# Sheet1.net
KiCad netlist of a schematic drawn in Altium Designer
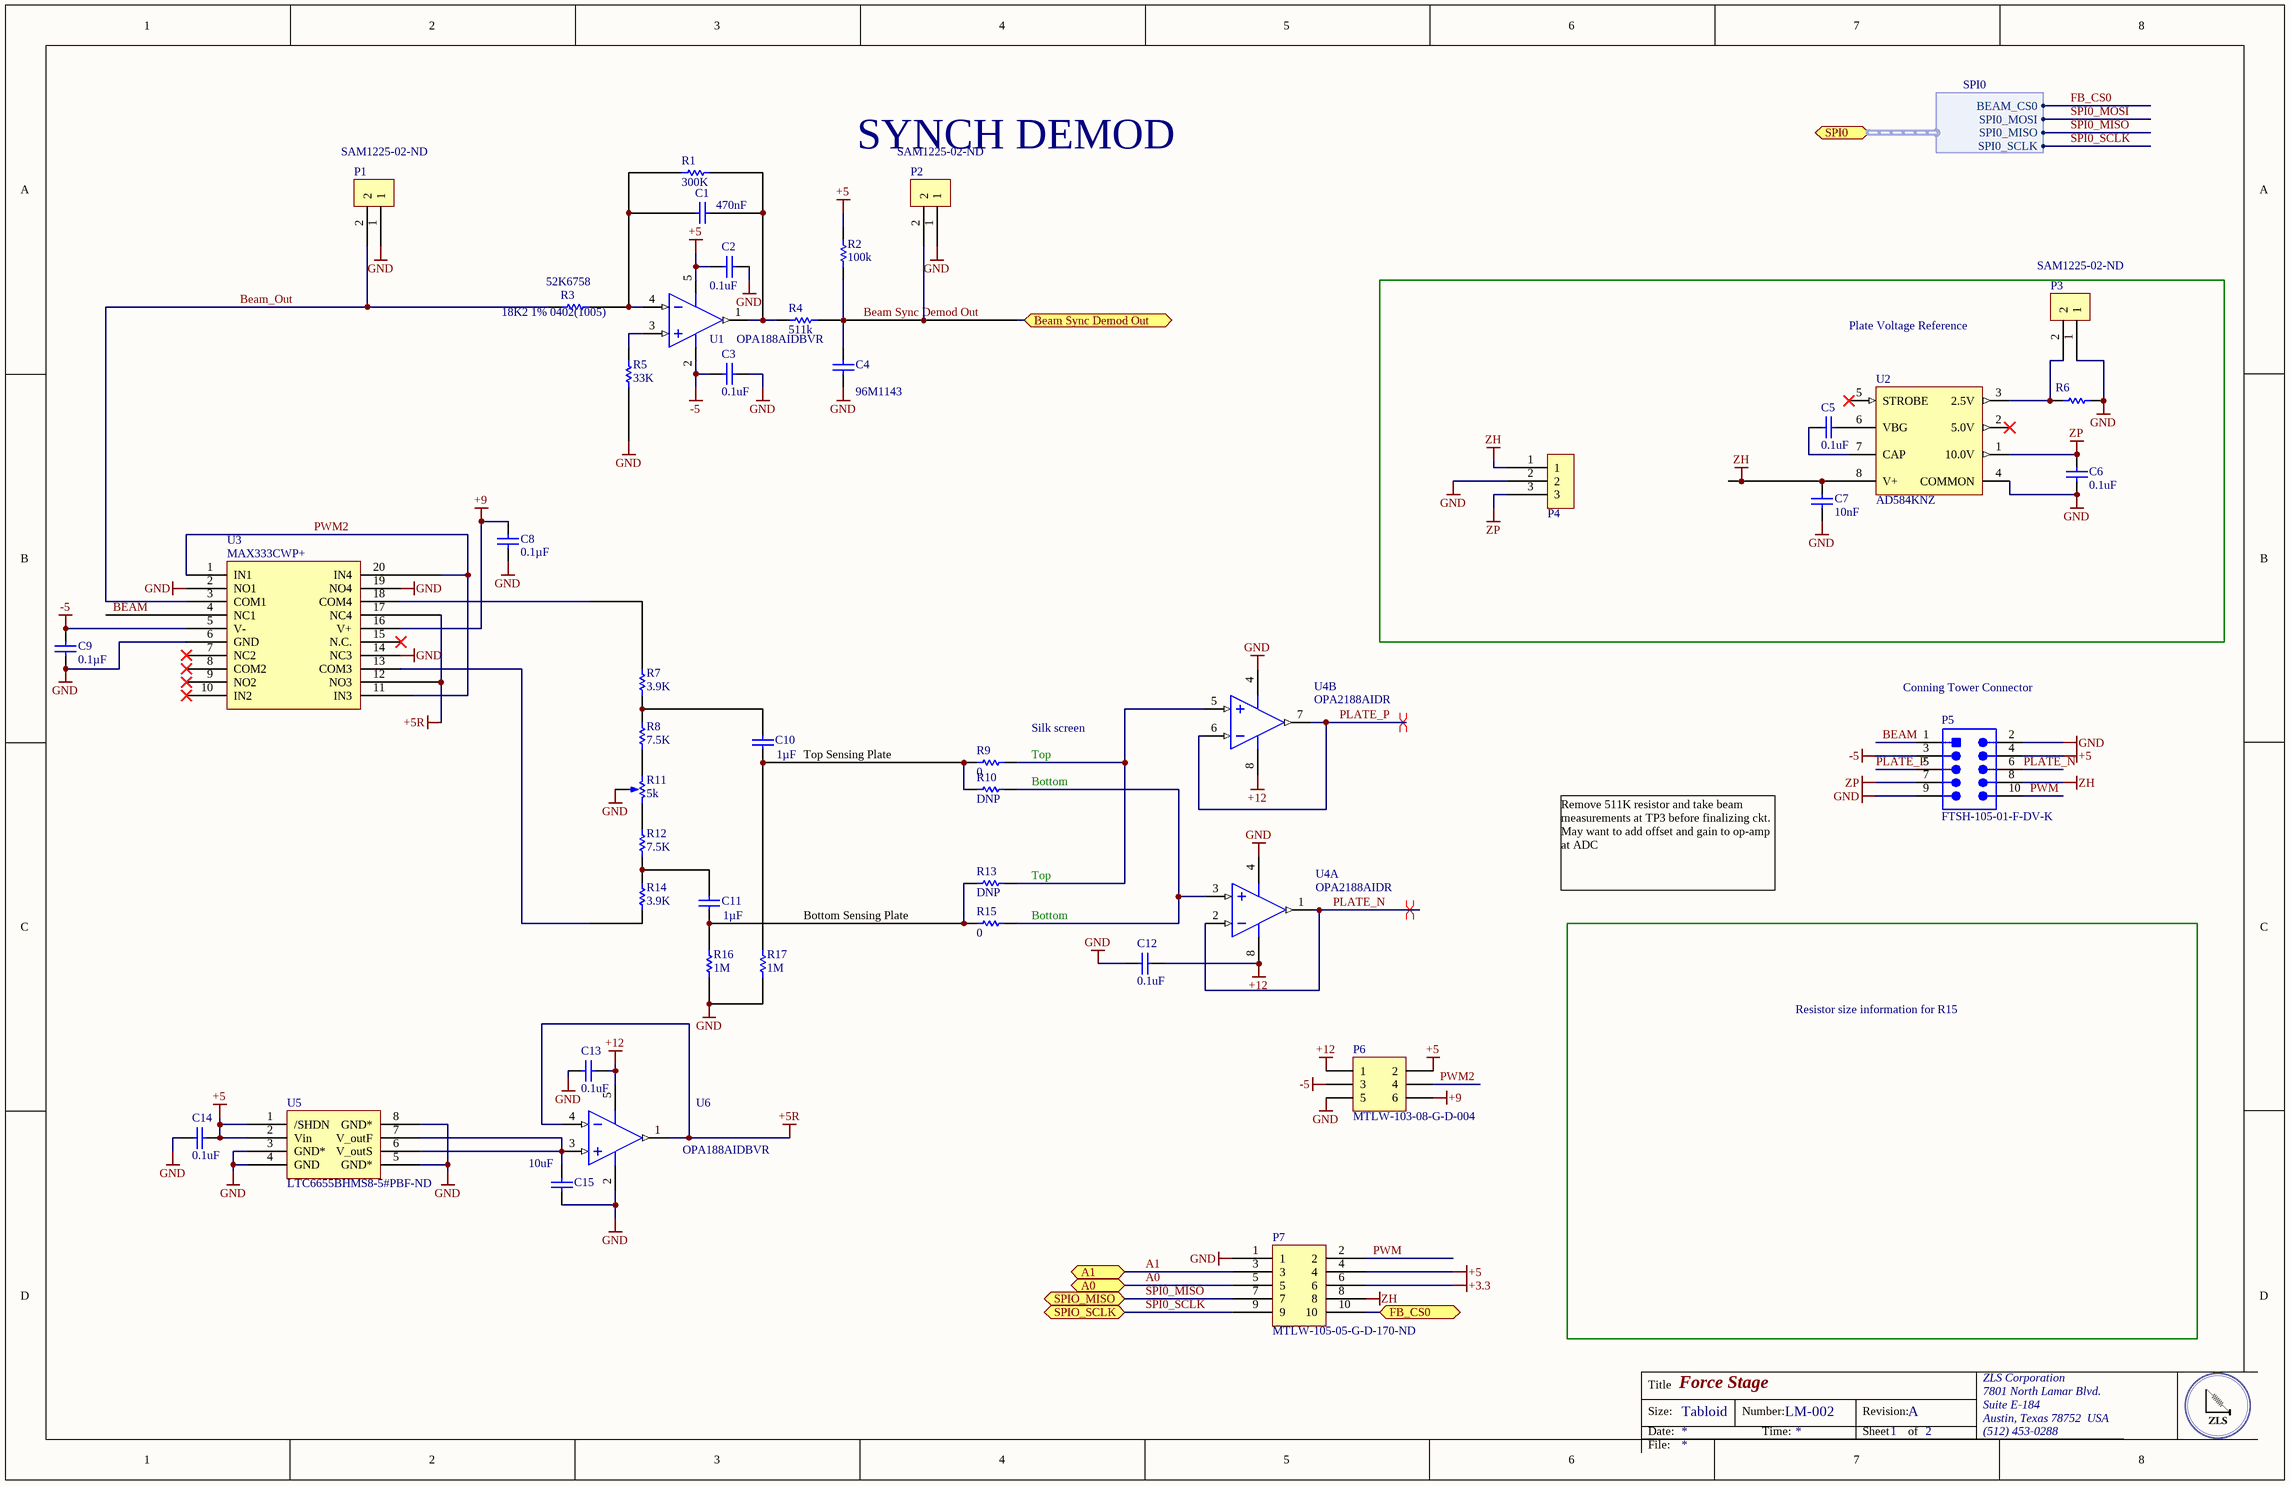
[diagram p0: Sheet1.SchDoc]

(export (version "E")
  (design (tool "Eeschema 10.0.6"))
  (components
    (comp (ref "C1")
      (value "~")
      (footprint "CAPC0402(1005)60_L")
      (fields
        (field (name "MANUFACTURER") "TDK")
        (field (name "MANUFACTURER PART NUMBER") "C1005X5R1E474M050BB")
        (field (name "TOLERANCE") "20%")
        (field (name "CAPACITANCE") "470nF")
      )
      (libsource (lib "Altium Content Vault") (part "CMP-1034-01343-1"))
    )
    (comp (ref "C2")
      (value "0.1uF")
      (footprint "CAPC0402(1005)60_L")
      (description "CAP CER 0.1UF 10V X7R 0402")
      (fields
        (field (name "MANUFACTURER") "Murata Electronics North America")
        (field (name "MANUFACTURER PART NUMBER") "GRM155R71A104KA01D")
      )
      (libsource (lib "Altium Content Vault") (part "CMP-1034-00252-1"))
    )
    (comp (ref "C3")
      (value "0.1uF")
      (footprint "CAPC0402(1005)60_L")
      (description "CAP CER 0.1UF 10V X7R 0402")
      (fields
        (field (name "MANUFACTURER") "Murata Electronics North America")
        (field (name "MANUFACTURER PART NUMBER") "GRM155R71A104KA01D")
      )
      (libsource (lib "Altium Content Vault") (part "CMP-1034-00252-1"))
    )
    (comp (ref "C4")
      (value "~")
      (footprint "CAPC0402(1005)60_L")
      (fields
        (field (name "SUPPLIER PART NUMBER 1") "96M1143")
        (field (name "MANUFACTURER") "AVX")
        (field (name "MANUFACTURER PART NUMBER") "04025A220JAT2A")
      )
      (libsource (lib "Altium Content Vault") (part "CMP-1034-01343-1"))
    )
    (comp (ref "C5")
      (value "0.1uF")
      (footprint "CAPC0402(1005)60_L")
      (description "CAP CER 0.1UF 10V X7R 0402")
      (fields
        (field (name "MANUFACTURER") "Murata Electronics North America")
        (field (name "MANUFACTURER PART NUMBER") "GRM155R71A104KA01D")
      )
      (libsource (lib "Altium Content Vault") (part "CMP-1034-00252-1"))
    )
    (comp (ref "C6")
      (value "0.1uF")
      (footprint "CAPC0402(1005)60_L")
      (description "CAP CER 0.1UF 10V X7R 0402")
      (fields
        (field (name "MANUFACTURER") "Murata Electronics North America")
        (field (name "MANUFACTURER PART NUMBER") "GRM155R71A104KA01D")
      )
      (libsource (lib "Altium Content Vault") (part "CMP-1034-00252-1"))
    )
    (comp (ref "C7")
      (value "Multilayer Ceramic Capacitors MLCC - SMD/SMT 0.01uF 50volts 10% X7R")
      (footprint "CAPC0805(2012)145_N")
      (fields
        (field (name "MANUFACTURER") "Kemet")
        (field (name "MANUFACTURER PART NUMBER") "C0805C103K5RACAUTO")
        (field (name "CAPACITANCE") "10nF")
        (field (name "TOLERANCE") "10%")
      )
      (libsource (lib "Altium Content Vault") (part "CMP-1036-04795-1"))
    )
    (comp (ref "C8")
      (value "CAP CER 0.1UF 25V X7R 0805")
      (footprint "CAPC0805(2012)145_N")
      (fields
        (field (name "MANUFACTURER") "Murata Electronics North America")
        (field (name "MANUFACTURER PART NUMBER") "GRM21BR71E104KA01L")
        (field (name "CAPACITANCE") "0.1µF")
        (field (name "TOLERANCE") "±10%")
      )
      (libsource (lib "Altium Content Vault") (part "CMP-1036-04795-1"))
    )
    (comp (ref "C9")
      (value "CAP CER 0.1UF 25V X7R 0805")
      (footprint "CAPC0805(2012)145_N")
      (fields
        (field (name "MANUFACTURER") "Murata Electronics North America")
        (field (name "MANUFACTURER PART NUMBER") "GRM21BR71E104KA01L")
        (field (name "CAPACITANCE") "0.1µF")
        (field (name "TOLERANCE") "±10%")
      )
      (libsource (lib "Altium Content Vault") (part "CMP-1036-04795-1"))
    )
    (comp (ref "C10")
      (value "CAP CER 1UF 25V X7R 0805")
      (footprint "CAPC0805(2012)155_L")
      (fields
        (field (name "MANUFACTURER") "Murata Electronics North America")
        (field (name "MANUFACTURER PART NUMBER") "GRM21BR71E105KA99L")
        (field (name "CAPACITANCE") "1µF")
        (field (name "TOLERANCE") "±10%")
      )
      (libsource (lib "Altium Content Vault") (part "CMP-1036-04882-1"))
    )
    (comp (ref "C11")
      (value "CAP CER 1UF 25V X7R 0805")
      (footprint "CAPC0805(2012)155_L")
      (fields
        (field (name "MANUFACTURER") "Murata Electronics North America")
        (field (name "MANUFACTURER PART NUMBER") "GRM21BR71E105KA99L")
        (field (name "CAPACITANCE") "1µF")
        (field (name "TOLERANCE") "±10%")
      )
      (libsource (lib "Altium Content Vault") (part "CMP-1036-04882-1"))
    )
    (comp (ref "C12")
      (value "0.1uF")
      (footprint "CAPC0402(1005)60_L")
      (description "CAP CER 0.1UF 10V X7R 0402")
      (fields
        (field (name "MANUFACTURER") "Murata Electronics North America")
        (field (name "MANUFACTURER PART NUMBER") "GRM155R71A104KA01D")
      )
      (libsource (lib "Altium Content Vault") (part "CMP-1034-00252-1"))
    )
    (comp (ref "C13")
      (value "0.1uF")
      (footprint "CAPC0402(1005)60_L")
      (description "CAP CER 0.1UF 10V X7R 0402")
      (fields
        (field (name "MANUFACTURER") "Murata Electronics North America")
        (field (name "MANUFACTURER PART NUMBER") "GRM155R71A104KA01D")
      )
      (libsource (lib "Altium Content Vault") (part "CMP-1034-00252-1"))
    )
    (comp (ref "C14")
      (value "0.1uF")
      (footprint "CAPC0402(1005)60_L")
      (description "CAP CER 0.1UF 10V X7R 0402")
      (fields
        (field (name "MANUFACTURER") "Murata Electronics North America")
        (field (name "MANUFACTURER PART NUMBER") "GRM155R71A104KA01D")
      )
      (libsource (lib "Altium Content Vault") (part "CMP-1034-00252-1"))
    )
    (comp (ref "C15")
      (value "10uF")
      (footprint "CAPC1812(4532)250_N")
      (description "CAP FILM 10UF 20% 16VDC 1812")
      (fields (field (name "TOLERANCE") "Â±10%") (field (name "MANUFACTURER") "Rubycon"))
      (libsource (lib "Altium Content Vault") (part "CMP-1040-01653-1"))
    )
    (comp (ref "P1")
      (value "SSW-102-02-G-S-RA")
      (footprint "SSW-102-02-G-S-RA")
      (fields (field (name "SUPPLIER PART NUMBER 1") "SAM1225-02-ND"))
      (libsource (lib "ZLS_Schematic_lib") (part "SSW-102-02-G-S-RA"))
    )
    (comp (ref "P2")
      (value "SSW-102-02-G-S-RA")
      (footprint "SSW-102-02-G-S-RA")
      (fields (field (name "SUPPLIER PART NUMBER 1") "SAM1225-02-ND"))
      (libsource (lib "ZLS_Schematic_lib") (part "SSW-102-02-G-S-RA"))
    )
    (comp (ref "P3")
      (value "SSW-102-02-G-S-RA")
      (footprint "SSW-102-02-G-S-RA")
      (fields (field (name "SUPPLIER PART NUMBER 1") "SAM1225-02-ND"))
      (libsource (lib "ZLS_Schematic_lib") (part "SSW-102-02-G-S-RA"))
    )
    (comp (ref "P4")
      (value "SSW-103-02-G-S-RA")
      (footprint "SSW-103-02-G-S-RA")
      (libsource (lib "ZLS_Schematic_lib") (part "SSW-103-02-G-S-RA"))
    )
    (comp (ref "P5")
      (value "FTSH-105-01-F-DV-K")
      (footprint "SMTC-FTSH-105-01-L-DV-K_V")
      (description "Male Header, Pitch 1.27 mm, 2 x 5 Position, Height 6.12 mm, RoHS, Tube")
      (fields (field (name "MANUFACTURER") "Samtec"))
      (libsource (lib "Altium Content Vault") (part "CN-2P-M-R10"))
    )
    (comp (ref "P6")
      (value "MTLW-103-08-G-D-004")
      (footprint "MTLW-103-08-G-D-004")
      (description "Header, 3-Pin, Dual row")
      (libsource (lib "Miscellaneous Connectors") (part "Header 3X2"))
    )
    (comp (ref "P7")
      (value "TLW-105-05-G-D")
      (footprint "TLW-105-05-G-D")
      (fields
        (field (name "SUPPLIER PART NUMBER 1") "MTLW-105-05-G-D-170-ND")
        (field (name "MANUFACTURER") "Samtec Inc.")
        (field (name "MANUFACTURER PART NUMBER") "MTLW-105-05-G-D-170")
      )
      (libsource (lib "ZLS_Schematic_lib") (part "TLW-105-05-G-D"))
    )
    (comp (ref "R1")
      (value "300K")
      (footprint "RESC0402(1005)_M")
      (libsource (lib "Altium Content Vault") (part "CMP-1011-00651-1"))
    )
    (comp (ref "R2")
      (value "100k")
      (footprint "RESC0402(1005)_M")
      (description "RES SMD 100K OHM 1% 1/8W 0402")
      (fields
        (field (name "MANUFACTURER") "Vishay Dale")
        (field (name "MANUFACTURER PART NUMBER") "CRCW0402100KFKEDHP")
      )
      (libsource (lib "Altium Content Vault") (part "CMP-1011-00651-1"))
    )
    (comp (ref "R3")
      (value "18K2 1% 0402(1005)")
      (footprint "RESC0402(1005)_M")
      (description "18K2 0.063W 1% 0402 (1005 Metric)  SMD")
      (fields
        (field (name "SUPPLIER PART NUMBER 1") "52K6758")
        (field (name "MANUFACTURER") "VISHAY")
        (field (name "MANUFACTURER PART NUMBER") "CRCW040218K2FKED")
      )
      (libsource (lib "Altium Content Vault") (part "CMP-1011-00651-1"))
    )
    (comp (ref "R4")
      (value "511k")
      (footprint "RESC0402(1005)_M")
      (libsource (lib "Altium Content Vault") (part "CMP-1011-00651-1"))
    )
    (comp (ref "R5")
      (value "33K")
      (footprint "RESC0402(1005)_M")
      (libsource (lib "Altium Content Vault") (part "CMP-1011-00651-1"))
    )
    (comp (ref "R6")
      (value "TBD")
      (footprint "VH102K")
      (libsource (lib "altium-import") (part "root_0_CMP-1013-00393-1_"))
    )
    (comp (ref "R7")
      (value "3.9K")
      (footprint "RESC0402(1005)_M")
      (libsource (lib "Altium Content Vault") (part "CMP-1011-00463-1"))
    )
    (comp (ref "R8")
      (value "7.5K")
      (footprint "RESC0402(1005)_M")
      (libsource (lib "Altium Content Vault") (part "CMP-1011-00463-1"))
    )
    (comp (ref "R9")
      (value "0")
      (footprint "RESC0402(1005)_M")
      (libsource (lib "Altium Content Vault") (part "CMP-1011-00651-1"))
    )
    (comp (ref "R10")
      (value "DNP")
      (footprint "RESC0402(1005)_M")
      (libsource (lib "Altium Content Vault") (part "CMP-1011-00651-1"))
    )
    (comp (ref "R11")
      (value "TRIMMER 5K OHM 0.25W PC PIN")
      (footprint "Trimmer 2.54")
      (fields
        (field (name "MANUFACTURER") "Vishay Foil Resistors (Division of Vishay Precision Group)")
        (field (name "MANUFACTURER PART NUMBER") "Y00535K00000J0L")
        (field (name "RESISTANCE (OHMS)") "5k")
        (field (name "TOLERANCE") "±5%")
      )
      (libsource (lib "ZLS_Schematic_lib") (part "Trimmer"))
    )
    (comp (ref "R12")
      (value "7.5K")
      (footprint "RESC0402(1005)_M")
      (libsource (lib "Altium Content Vault") (part "CMP-1011-00463-1"))
    )
    (comp (ref "R13")
      (value "DNP")
      (footprint "RESC0402(1005)_M")
      (libsource (lib "Altium Content Vault") (part "CMP-1011-00651-1"))
    )
    (comp (ref "R14")
      (value "3.9K")
      (footprint "RESC0402(1005)_M")
      (libsource (lib "Altium Content Vault") (part "CMP-1011-00463-1"))
    )
    (comp (ref "R15")
      (value "0")
      (footprint "RESC0402(1005)_M")
      (libsource (lib "Altium Content Vault") (part "CMP-1011-00651-1"))
    )
    (comp (ref "R16")
      (value "1M")
      (footprint "RESC0402(1005)_M")
      (libsource (lib "Altium Content Vault") (part "CMP-1011-00463-1"))
    )
    (comp (ref "R17")
      (value "1M")
      (footprint "RESC0402(1005)_M")
      (libsource (lib "Altium Content Vault") (part "CMP-1011-00463-1"))
    )
    (comp (ref "U1")
      (value "OPA188AIDBVR")
      (footprint "DBV0005A_M")
      (fields (field (name "MANUFACTURER") "Texas Instruments"))
      (libsource (lib "Altium Content Vault") (part "CMP-0809-00005-2"))
    )
    (comp (ref "U2")
      (value "AD584KNZ")
      (footprint "ADI-N-8")
      (fields (field (name "MANUFACTURER") "Analog Devices"))
      (libsource (lib "Altium Content Vault") (part "ADI-AD584-N-8"))
    )
    (comp (ref "U3")
      (value "MAX333CWP+")
      (footprint "TSOP65P640X90-20N")
      (description "IC SWITCH QUAD SPDT 20TSSOP")
      (fields (field (name "MANUFACTURER") "Maxim") (field (name "MANUFACTURER PART NUMBER") "MAX333AEUP+"))
      (libsource (lib "ZLS_Schematic_lib") (part "MAX333CWP+"))
    )
    (comp (ref "U4")
      (value "OPA2188AIDR")
      (footprint "D0008A_L")
      (fields (field (name "MANUFACTURER") "Texas Instruments"))
      (libsource (lib "Altium Content Vault") (part "CMP-0272-00241-3"))
    )
    (comp (ref "U5")
      (value "LTC6655BHMS8-5#PBF")
      (footprint "TSOP65P490X110-8N")
      (fields
        (field (name "SUPPLIER PART NUMBER 1") "LTC6655BHMS8-5#PBF-ND")
        (field (name "MANUFACTURER") "Linear Technology")
        (field (name "TOLERANCE") "±0.025%")
      )
      (libsource (lib "ZLS_Schematic_lib") (part "LTC6655BHMS8-5#PBF"))
    )
    (comp (ref "U6")
      (value "OPA188AIDBVR")
      (footprint "DBV0005A_M")
      (fields (field (name "MANUFACTURER") "Texas Instruments"))
      (libsource (lib "Altium Content Vault") (part "CMP-0809-00005-2"))
    )
  )
  (nets
    (net (code "2") (name "+3.3") (class "Default")
      (node (ref "P7") (pin "6") (pinfunction "6_6") (pintype "passive"))
    )
    (net (code "3") (name "+5") (class "Default")
      (node (ref "C14") (pin "2") (pinfunction "2_2") (pintype "passive"))
      (node (ref "C2") (pin "1") (pinfunction "1_1") (pintype "passive"))
      (node (ref "P5") (pin "4") (pinfunction "4_4") (pintype "passive"))
      (node (ref "P6") (pin "2") (pinfunction "2_2") (pintype "passive"))
      (node (ref "P7") (pin "4") (pinfunction "4_4") (pintype "passive"))
      (node (ref "R2") (pin "2") (pinfunction "2_2") (pintype "passive"))
      (node (ref "U1") (pin "5") (pinfunction "V+_5") (pintype "power_in"))
      (node (ref "U5") (pin "1") (pinfunction "/SHDN_1") (pintype "passive"))
      (node (ref "U5") (pin "2") (pinfunction "Vin_2") (pintype "passive"))
    )
    (net (code "4") (name "+5R") (class "Default")
      (node (ref "U3") (pin "12") (pinfunction "NO3_12") (pintype "passive"))
      (node (ref "U3") (pin "17") (pinfunction "NC4_17") (pintype "passive"))
      (node (ref "U6") (pin "1") (pinfunction "OUT_1") (pintype "output"))
      (node (ref "U6") (pin "4") (pinfunction "IN-_4") (pintype "input"))
    )
    (net (code "5") (name "+9") (class "Default")
      (node (ref "C8") (pin "2") (pinfunction "2_2") (pintype "passive"))
      (node (ref "P6") (pin "6") (pinfunction "6_6") (pintype "passive"))
      (node (ref "U3") (pin "16") (pinfunction "V+_16") (pintype "power_in"))
    )
    (net (code "6") (name "+12") (class "Default")
      (node (ref "C12") (pin "2") (pinfunction "2_2") (pintype "passive"))
      (node (ref "C13") (pin "2") (pinfunction "2_2") (pintype "passive"))
      (node (ref "P6") (pin "1") (pinfunction "1_1") (pintype "passive"))
      (node (ref "U4") (pin "8") (pinfunction "V+_8") (pintype "power_in"))
      (node (ref "U6") (pin "5") (pinfunction "V+_5") (pintype "power_in"))
    )
    (net (code "7") (name "-5") (class "Default")
      (node (ref "C3") (pin "1") (pinfunction "1_1") (pintype "passive"))
      (node (ref "C9") (pin "1") (pinfunction "1_1") (pintype "passive"))
      (node (ref "P5") (pin "3") (pinfunction "3_3") (pintype "passive"))
      (node (ref "P6") (pin "3") (pinfunction "3_3") (pintype "passive"))
      (node (ref "U1") (pin "2") (pinfunction "V-_2") (pintype "power_in"))
      (node (ref "U3") (pin "5") (pinfunction "V-_5") (pintype "power_in"))
    )
    (net (code "8") (name "/A0") (class "Default")
      (node (ref "P7") (pin "5") (pinfunction "5_5") (pintype "passive"))
    )
    (net (code "9") (name "/A1") (class "Default")
      (node (ref "P7") (pin "3") (pinfunction "3_3") (pintype "passive"))
    )
    (net (code "10") (name "/BEAM") (class "Default")
      (node (ref "P5") (pin "1") (pinfunction "1_1") (pintype "passive"))
      (node (ref "U3") (pin "4") (pinfunction "NC1_4") (pintype "passive"))
    )
    (net (code "11") (name "/Beam Sync Demod Out") (class "Default")
      (node (ref "C4") (pin "2") (pinfunction "2_2") (pintype "passive"))
      (node (ref "P2") (pin "2") (pinfunction "2_2") (pintype "passive"))
      (node (ref "R2") (pin "1") (pinfunction "1_1") (pintype "passive"))
      (node (ref "R4") (pin "2") (pinfunction "2_2") (pintype "passive"))
    )
    (net (code "12") (name "/Beam_Out") (class "Default")
      (node (ref "P1") (pin "2") (pinfunction "2_2") (pintype "passive"))
      (node (ref "R3") (pin "1") (pinfunction "1_1") (pintype "passive"))
      (node (ref "U3") (pin "3") (pinfunction "COM1_3") (pintype "passive"))
    )
    (net (code "13") (name "/FB_CS0") (class "Default")
      (node (ref "P7") (pin "10") (pinfunction "10_10") (pintype "passive"))
    )
    (net (code "14") (name "/PLATE_N") (class "Default")
      (node (ref "P5") (pin "6") (pinfunction "6_6") (pintype "passive"))
      (node (ref "U4") (pin "1") (pinfunction "OUT_A_1") (pintype "output"))
      (node (ref "U4") (pin "2") (pinfunction "IN_A-_2") (pintype "input"))
    )
    (net (code "15") (name "/PLATE_P") (class "Default")
      (node (ref "P5") (pin "5") (pinfunction "5_5") (pintype "passive"))
      (node (ref "U4") (pin "6") (pinfunction "IN_B-_6") (pintype "input"))
      (node (ref "U4") (pin "7") (pinfunction "OUT_B_7") (pintype "output"))
    )
    (net (code "16") (name "/PWM") (class "Default")
      (node (ref "P5") (pin "10") (pinfunction "10_10") (pintype "passive"))
      (node (ref "P7") (pin "2") (pinfunction "2_2") (pintype "passive"))
    )
    (net (code "17") (name "/PWM2") (class "Default")
      (node (ref "P6") (pin "4") (pinfunction "4_4") (pintype "passive"))
      (node (ref "U3") (pin "1") (pinfunction "IN1_1") (pintype "passive"))
      (node (ref "U3") (pin "11") (pinfunction "IN3_11") (pintype "passive"))
      (node (ref "U3") (pin "20") (pinfunction "IN4_20") (pintype "passive"))
    )
    (net (code "18") (name "/SPI0_MISO") (class "Default")
      (node (ref "P7") (pin "7") (pinfunction "7_7") (pintype "passive"))
    )
    (net (code "20") (name "/SPI0_SCLK") (class "Default")
      (node (ref "P7") (pin "9") (pinfunction "9_9") (pintype "passive"))
    )
    (net (code "22") (name "GND") (class "Default")
      (node (ref "C12") (pin "1") (pinfunction "1_1") (pintype "passive"))
      (node (ref "C13") (pin "1") (pinfunction "1_1") (pintype "passive"))
      (node (ref "C14") (pin "1") (pinfunction "1_1") (pintype "passive"))
      (node (ref "C15") (pin "1") (pinfunction "1_1") (pintype "passive"))
      (node (ref "C2") (pin "2") (pinfunction "2_2") (pintype "passive"))
      (node (ref "C3") (pin "2") (pinfunction "2_2") (pintype "passive"))
      (node (ref "C4") (pin "1") (pinfunction "1_1") (pintype "passive"))
      (node (ref "C6") (pin "1") (pinfunction "1_1") (pintype "passive"))
      (node (ref "C7") (pin "2") (pinfunction "2_2") (pintype "passive"))
      (node (ref "C8") (pin "1") (pinfunction "1_1") (pintype "passive"))
      (node (ref "C9") (pin "2") (pinfunction "2_2") (pintype "passive"))
      (node (ref "P1") (pin "1") (pinfunction "1_1") (pintype "passive"))
      (node (ref "P2") (pin "1") (pinfunction "1_1") (pintype "passive"))
      (node (ref "P3") (pin "1") (pinfunction "1_1") (pintype "passive"))
      (node (ref "P4") (pin "2") (pinfunction "2_2") (pintype "passive"))
      (node (ref "P5") (pin "2") (pinfunction "2_2") (pintype "passive"))
      (node (ref "P5") (pin "9") (pinfunction "9_9") (pintype "passive"))
      (node (ref "P6") (pin "5") (pinfunction "5_5") (pintype "passive"))
      (node (ref "P7") (pin "1") (pinfunction "1_1") (pintype "passive"))
      (node (ref "R11") (pin "2") (pinfunction "b_2") (pintype "passive"))
      (node (ref "R16") (pin "1") (pinfunction "1_1") (pintype "passive"))
      (node (ref "R17") (pin "1") (pinfunction "1_1") (pintype "passive"))
      (node (ref "R5") (pin "1") (pinfunction "1_1") (pintype "passive"))
      (node (ref "R6") (pin "2") (pinfunction "2_2") (pintype "passive"))
      (node (ref "U2") (pin "4") (pinfunction "COMMON_4") (pintype "passive"))
      (node (ref "U3") (pin "14") (pinfunction "NC3_14") (pintype "passive"))
      (node (ref "U3") (pin "19") (pinfunction "NO4_19") (pintype "passive"))
      (node (ref "U3") (pin "2") (pinfunction "NO1_2") (pintype "passive"))
      (node (ref "U3") (pin "6") (pinfunction "GND_6") (pintype "passive"))
      (node (ref "U4") (pin "4") (pinfunction "V-_4") (pintype "power_in"))
      (node (ref "U5") (pin "3") (pinfunction "GND*_3") (pintype "passive"))
      (node (ref "U5") (pin "4") (pinfunction "GND_4") (pintype "passive"))
      (node (ref "U5") (pin "5") (pinfunction "GND*_5") (pintype "passive"))
      (node (ref "U5") (pin "8") (pinfunction "GND*_8") (pintype "passive"))
      (node (ref "U6") (pin "2") (pinfunction "V-_2") (pintype "power_in"))
    )
    (net (code "23") (name "Net-(C10-Pad1)") (class "Default")
      (node (ref "C10") (pin "1") (pinfunction "1_1") (pintype "passive"))
      (node (ref "R10") (pin "2") (pinfunction "2_2") (pintype "passive"))
      (node (ref "R17") (pin "2") (pinfunction "2_2") (pintype "passive"))
      (node (ref "R9") (pin "2") (pinfunction "2_2") (pintype "passive"))
    )
    (net (code "24") (name "Net-(C10-Pad2)") (class "Default")
      (node (ref "C10") (pin "2") (pinfunction "2_2") (pintype "passive"))
      (node (ref "R7") (pin "1") (pinfunction "1_1") (pintype "passive"))
      (node (ref "R8") (pin "2") (pinfunction "2_2") (pintype "passive"))
    )
    (net (code "25") (name "Net-(C11-Pad1)") (class "Default")
      (node (ref "C11") (pin "1") (pinfunction "1_1") (pintype "passive"))
      (node (ref "R13") (pin "2") (pinfunction "2_2") (pintype "passive"))
      (node (ref "R15") (pin "2") (pinfunction "2_2") (pintype "passive"))
      (node (ref "R16") (pin "2") (pinfunction "2_2") (pintype "passive"))
    )
    (net (code "26") (name "Net-(C11-Pad2)") (class "Default")
      (node (ref "C11") (pin "2") (pinfunction "2_2") (pintype "passive"))
      (node (ref "R12") (pin "1") (pinfunction "1_1") (pintype "passive"))
      (node (ref "R14") (pin "2") (pinfunction "2_2") (pintype "passive"))
    )
    (net (code "27") (name "Net-(R11-a)") (class "Default")
      (node (ref "R11") (pin "1") (pinfunction "a_1") (pintype "passive"))
      (node (ref "R8") (pin "1") (pinfunction "1_1") (pintype "passive"))
    )
    (net (code "28") (name "Net-(R11-c)") (class "Default")
      (node (ref "R11") (pin "3") (pinfunction "c_3") (pintype "passive"))
      (node (ref "R12") (pin "2") (pinfunction "2_2") (pintype "passive"))
    )
    (net (code "29") (name "Net-(U1-IN+)") (class "Default")
      (node (ref "R5") (pin "2") (pinfunction "2_2") (pintype "passive"))
      (node (ref "U1") (pin "3") (pinfunction "IN+_3") (pintype "input"))
    )
    (net (code "30") (name "Net-(U1-IN-)") (class "Default")
      (node (ref "C1") (pin "1") (pinfunction "1_1") (pintype "passive"))
      (node (ref "R1") (pin "1") (pinfunction "1_1") (pintype "passive"))
      (node (ref "R3") (pin "2") (pinfunction "2_2") (pintype "passive"))
      (node (ref "U1") (pin "4") (pinfunction "IN-_4") (pintype "input"))
    )
    (net (code "31") (name "Net-(U1-OUT)") (class "Default")
      (node (ref "C1") (pin "2") (pinfunction "2_2") (pintype "passive"))
      (node (ref "R1") (pin "2") (pinfunction "2_2") (pintype "passive"))
      (node (ref "R4") (pin "1") (pinfunction "1_1") (pintype "passive"))
      (node (ref "U1") (pin "1") (pinfunction "OUT_1") (pintype "output"))
    )
    (net (code "32") (name "Net-(U2-2.5V)") (class "Default")
      (node (ref "P3") (pin "2") (pinfunction "2_2") (pintype "passive"))
      (node (ref "R6") (pin "1") (pinfunction "1_1") (pintype "passive"))
      (node (ref "U2") (pin "3") (pinfunction "2.5V_3") (pintype "output"))
    )
    (net (code "33") (name "Net-(U2-CAP)") (class "Default")
      (node (ref "C5") (pin "1") (pinfunction "1_1") (pintype "passive"))
      (node (ref "U2") (pin "7") (pinfunction "CAP_7") (pintype "passive"))
    )
    (net (code "34") (name "Net-(U2-VBG)") (class "Default")
      (node (ref "C5") (pin "2") (pinfunction "2_2") (pintype "passive"))
      (node (ref "U2") (pin "6") (pinfunction "VBG_6") (pintype "passive"))
    )
    (net (code "35") (name "Net-(U3-COM3)") (class "Default")
      (node (ref "R14") (pin "1") (pinfunction "1_1") (pintype "passive"))
      (node (ref "U3") (pin "13") (pinfunction "COM3_13") (pintype "passive"))
    )
    (net (code "36") (name "Net-(U3-COM4)") (class "Default")
      (node (ref "R7") (pin "2") (pinfunction "2_2") (pintype "passive"))
      (node (ref "U3") (pin "18") (pinfunction "COM4_18") (pintype "passive"))
    )
    (net (code "37") (name "Net-(U4A-IN_A+)") (class "Default")
      (node (ref "R10") (pin "1") (pinfunction "1_1") (pintype "passive"))
      (node (ref "R15") (pin "1") (pinfunction "1_1") (pintype "passive"))
      (node (ref "U4") (pin "3") (pinfunction "IN_A+_3") (pintype "input"))
    )
    (net (code "38") (name "Net-(U4B-IN_B+)") (class "Default")
      (node (ref "R13") (pin "1") (pinfunction "1_1") (pintype "passive"))
      (node (ref "R9") (pin "1") (pinfunction "1_1") (pintype "passive"))
      (node (ref "U4") (pin "5") (pinfunction "IN_B+_5") (pintype "input"))
    )
    (net (code "39") (name "Net-(U5-V_outF)") (class "Default")
      (node (ref "C15") (pin "2") (pinfunction "2_2") (pintype "passive"))
      (node (ref "U5") (pin "6") (pinfunction "V_outS_6") (pintype "passive"))
      (node (ref "U5") (pin "7") (pinfunction "V_outF_7") (pintype "passive"))
      (node (ref "U6") (pin "3") (pinfunction "IN+_3") (pintype "input"))
    )
    (net (code "40") (name "ZH") (class "Default")
      (node (ref "C7") (pin "1") (pinfunction "1_1") (pintype "passive"))
      (node (ref "P4") (pin "1") (pinfunction "1_1") (pintype "passive"))
      (node (ref "P5") (pin "8") (pinfunction "8_8") (pintype "passive"))
      (node (ref "P7") (pin "8") (pinfunction "8_8") (pintype "passive"))
      (node (ref "U2") (pin "8") (pinfunction "V+_8") (pintype "power_in"))
    )
    (net (code "41") (name "ZP") (class "Default")
      (node (ref "C6") (pin "2") (pinfunction "2_2") (pintype "passive"))
      (node (ref "P4") (pin "3") (pinfunction "3_3") (pintype "passive"))
      (node (ref "P5") (pin "7") (pinfunction "7_7") (pintype "passive"))
      (node (ref "U2") (pin "1") (pinfunction "10.0V_1") (pintype "output"))
    )
    (net (code "42") (name "unconnected-(U2-5.0V-Pad2)") (class "Default")
      (node (ref "U2") (pin "2") (pinfunction "5.0V_2") (pintype "output+no_connect"))
    )
    (net (code "43") (name "unconnected-(U2-STROBE-Pad5)") (class "Default")
      (node (ref "U2") (pin "5") (pinfunction "STROBE_5") (pintype "input+no_connect"))
    )
    (net (code "44") (name "unconnected-(U3-COM2-Pad8)") (class "Default")
      (node (ref "U3") (pin "8") (pinfunction "COM2_8") (pintype "passive+no_connect"))
    )
    (net (code "45") (name "unconnected-(U3-IN2-Pad10)") (class "Default")
      (node (ref "U3") (pin "10") (pinfunction "IN2_10") (pintype "passive+no_connect"))
    )
    (net (code "46") (name "unconnected-(U3-N.C.-Pad15)") (class "Default")
      (node (ref "U3") (pin "15") (pinfunction "N.C._15") (pintype "passive+no_connect"))
    )
    (net (code "47") (name "unconnected-(U3-NC2-Pad7)") (class "Default")
      (node (ref "U3") (pin "7") (pinfunction "NC2_7") (pintype "passive+no_connect"))
    )
    (net (code "48") (name "unconnected-(U3-NO2-Pad9)") (class "Default")
      (node (ref "U3") (pin "9") (pinfunction "NO2_9") (pintype "passive+no_connect"))
    )
  )
)
